# Earphone-5.net
KiCad netlist of a schematic drawn in Altium Designer
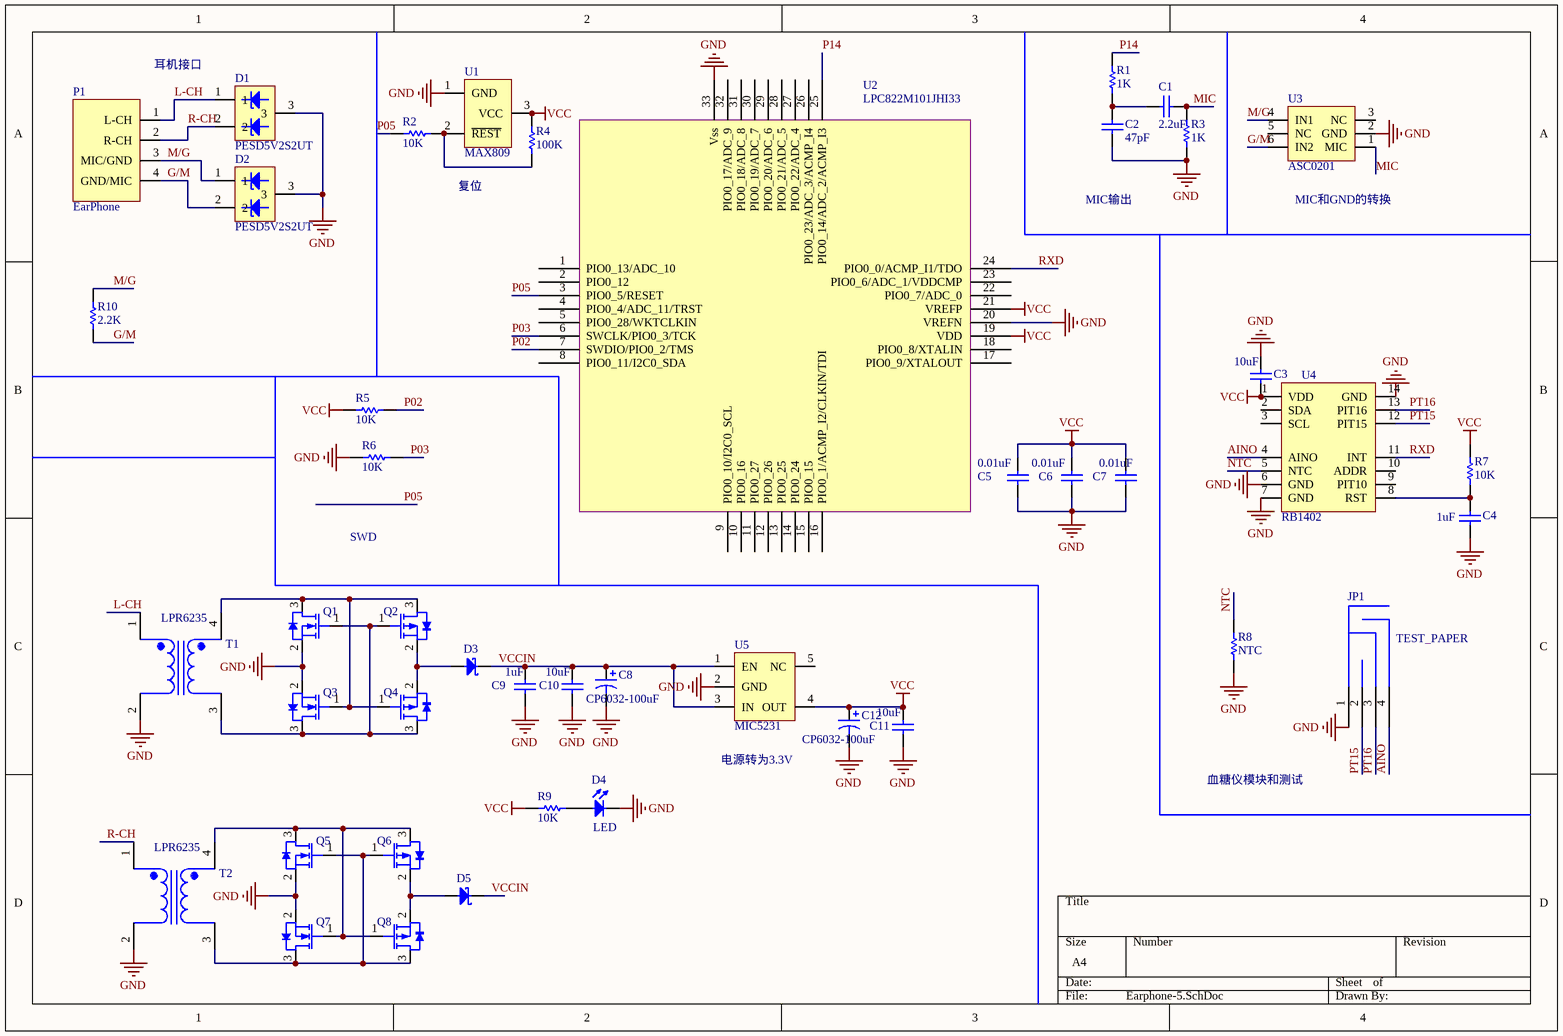
[diagram p0: Earphone-5.SchDoc]

(export (version "E")
  (design (tool "Eeschema 10.0.6"))
  (components
    (comp (ref "C1") (value "2.2uF") (footprint "0402C") (libsource (lib "Schlib1") (part "CAP")))
    (comp (ref "C2") (value "47pF") (footprint "0402C") (libsource (lib "Schlib1") (part "CAP")))
    (comp (ref "C3") (value "10uF") (footprint "0402C") (libsource (lib "Schlib1") (part "CAP")))
    (comp (ref "C4") (value "1uF") (footprint "0402C") (libsource (lib "Schlib1") (part "CAP")))
    (comp (ref "C5") (value "0.01uF") (footprint "0402C") (libsource (lib "Schlib1") (part "CAP")))
    (comp (ref "C6") (value "0.01uF") (footprint "0402C") (libsource (lib "Schlib1") (part "CAP")))
    (comp (ref "C7") (value "0.01uF") (footprint "0402C") (libsource (lib "Schlib1") (part "CAP")))
    (comp (ref "C8")
      (value "CP6032-100uF")
      (footprint "T3216-18[A]")
      (libsource (lib "Schlib1") (part "CAP POL2"))
    )
    (comp (ref "C9") (value "1uF") (footprint "0402C") (libsource (lib "Schlib1") (part "CAP")))
    (comp (ref "C10") (value "10uF") (footprint "0402C") (libsource (lib "Schlib1") (part "CAP")))
    (comp (ref "C11") (value "10uF") (footprint "0402C") (libsource (lib "Schlib1") (part "CAP")))
    (comp (ref "C12")
      (value "CP6032-100uF")
      (footprint "T3216-18[A]")
      (libsource (lib "Schlib1") (part "CAP POL2"))
    )
    (comp (ref "D1")
      (value "PESD5V2S2UT")
      (footprint "SOT23")
      (description "SOT23")
      (libsource (lib "Schlib1") (part "PESD5V2S2UT"))
    )
    (comp (ref "D2")
      (value "PESD5V2S2UT")
      (footprint "SOT23")
      (description "SOT23")
      (libsource (lib "Schlib1") (part "PESD5V2S2UT"))
    )
    (comp (ref "D3")
      (value "PMEG4002EJ")
      (footprint "SOD323")
      (description "SOD323F")
      (libsource (lib "Schlib1") (part "PMEG4002EJ"))
    )
    (comp (ref "D4") (value "LED") (footprint "0603L") (libsource (lib "Schlib1") (part "LED")))
    (comp (ref "D5")
      (value "PMEG4002EJ")
      (footprint "SOD323")
      (description "SOD323F")
      (libsource (lib "Schlib1") (part "PMEG4002EJ"))
    )
    (comp (ref "JP1")
      (value "TEST_PAPER")
      (footprint "TEST_PAPER")
      (libsource (lib "Schlib1") (part "TEST_PAPER"))
    )
    (comp (ref "P1") (value "EarPhone") (footprint "EarPhone") (libsource (lib "Schlib1") (part "EarPhone")))
    (comp (ref "Q1")
      (value "N-MOSFET")
      (footprint "SOT23")
      (description "4N80 N-Channel MOSFET")
      (libsource (lib "Schlib1") (part "N-MOSFET"))
    )
    (comp (ref "Q2")
      (value "P-MOSFET")
      (footprint "SOT23")
      (description "P-Channel MOSFET")
      (libsource (lib "Schlib1") (part "P-MOSFET"))
    )
    (comp (ref "Q3")
      (value "N-MOSFET")
      (footprint "SOT23")
      (description "4N80 N-Channel MOSFET")
      (libsource (lib "Schlib1") (part "N-MOSFET"))
    )
    (comp (ref "Q4")
      (value "P-MOSFET")
      (footprint "SOT23")
      (description "P-Channel MOSFET")
      (libsource (lib "") (part "P-MOSFET_1"))
    )
    (comp (ref "Q5")
      (value "N-MOSFET")
      (footprint "SOT23")
      (description "4N80 N-Channel MOSFET")
      (libsource (lib "Schlib1") (part "N-MOSFET"))
    )
    (comp (ref "Q6")
      (value "P-MOSFET")
      (footprint "SOT23")
      (description "P-Channel MOSFET")
      (libsource (lib "Schlib1") (part "P-MOSFET"))
    )
    (comp (ref "Q7")
      (value "N-MOSFET")
      (footprint "SOT23")
      (description "4N80 N-Channel MOSFET")
      (libsource (lib "Schlib1") (part "N-MOSFET"))
    )
    (comp (ref "Q8")
      (value "P-MOSFET")
      (footprint "SOT23")
      (description "P-Channel MOSFET")
      (libsource (lib "") (part "P-MOSFET_1"))
    )
    (comp (ref "R1") (value "1K") (footprint "0402R") (libsource (lib "Schlib1") (part "RES")))
    (comp (ref "R2") (value "10K") (footprint "0402R") (libsource (lib "Schlib1") (part "RES")))
    (comp (ref "R3") (value "1K") (footprint "0402R") (libsource (lib "Schlib1") (part "RES")))
    (comp (ref "R4") (value "100K") (footprint "0402R") (libsource (lib "Schlib1") (part "RES")))
    (comp (ref "R5") (value "10K") (footprint "0402R") (libsource (lib "Schlib1") (part "RES")))
    (comp (ref "R6") (value "10K") (footprint "0402R") (libsource (lib "Schlib1") (part "RES")))
    (comp (ref "R7") (value "10K") (footprint "0402R") (libsource (lib "Schlib1") (part "RES")))
    (comp (ref "R8") (value "NTC") (footprint "0603R") (libsource (lib "Schlib1") (part "RES")))
    (comp (ref "R9") (value "10K") (footprint "0402R") (libsource (lib "Schlib1") (part "RES")))
    (comp (ref "R10") (value "2.2K") (footprint "0402R") (libsource (lib "Schlib1") (part "RES")))
    (comp (ref "T1") (value "LPR6235") (footprint "Trans EMI") (libsource (lib "Schlib1") (part "Trans EMI")))
    (comp (ref "T2") (value "LPR6235") (footprint "Trans EMI") (libsource (lib "Schlib1") (part "Trans EMI")))
    (comp (ref "U1")
      (value "MAX809")
      (footprint "SOT23")
      (description "SOT23")
      (libsource (lib "Schlib1") (part "MAX809"))
    )
    (comp (ref "U2")
      (value "LPC822M101JHI33")
      (footprint "QFN50P500X500X100-33N")
      (libsource (lib "Schlib1") (part "LPC822M101JHI33"))
    )
    (comp (ref "U3")
      (value "ASC0201")
      (footprint "SOT23-6")
      (description "SOT23-6")
      (libsource (lib "Schlib1") (part "ASC0201"))
    )
    (comp (ref "U4") (value "RB1402") (footprint "RB1402") (libsource (lib "Schlib1") (part "RB1402")))
    (comp (ref "U5") (value "MIC5231") (footprint "SOT23-5") (libsource (lib "Schlib1") (part "MIC5231")))
  )
  (nets
    (net (code "1") (name "/AINO") (class "Default")
      (node (ref "JP1") (pin "4") (pinfunction "P_4") (pintype "passive"))
      (node (ref "U4") (pin "4") (pinfunction "AINO_4") (pintype "passive"))
    )
    (net (code "2") (name "/G{slash}M") (class "Default")
      (node (ref "D2") (pin "2") (pinfunction "2_2") (pintype "passive"))
      (node (ref "P1") (pin "4") (pinfunction "GND/MIC_4") (pintype "passive"))
      (node (ref "R10") (pin "1") (pinfunction "1_1") (pintype "passive"))
      (node (ref "U3") (pin "6") (pinfunction "IN2_6") (pintype "passive"))
    )
    (net (code "3") (name "/L-CH") (class "Default")
      (node (ref "D1") (pin "1") (pinfunction "1_1") (pintype "passive"))
      (node (ref "P1") (pin "1") (pinfunction "L-CH_1") (pintype "passive"))
      (node (ref "T1") (pin "1") (pinfunction "1_1") (pintype "passive"))
    )
    (net (code "4") (name "/MIC") (class "Default")
      (node (ref "C1") (pin "1") (pinfunction "1_1") (pintype "passive"))
      (node (ref "R3") (pin "1") (pinfunction "1_1") (pintype "passive"))
      (node (ref "U3") (pin "1") (pinfunction "MIC_1") (pintype "passive"))
    )
    (net (code "5") (name "/M{slash}G") (class "Default")
      (node (ref "D2") (pin "1") (pinfunction "1_1") (pintype "passive"))
      (node (ref "P1") (pin "3") (pinfunction "MIC/GND_3") (pintype "passive"))
      (node (ref "R10") (pin "2") (pinfunction "2_2") (pintype "passive"))
      (node (ref "U3") (pin "4") (pinfunction "IN1_4") (pintype "passive"))
    )
    (net (code "6") (name "/NTC") (class "Default")
      (node (ref "R8") (pin "2") (pinfunction "2_2") (pintype "passive"))
      (node (ref "U4") (pin "5") (pinfunction "NTC_5") (pintype "passive"))
    )
    (net (code "7") (name "/P02") (class "Default")
      (node (ref "R5") (pin "2") (pinfunction "2_2") (pintype "passive"))
      (node (ref "U2") (pin "7") (pinfunction "SWDIO/PIO0_2/TMS_7") (pintype "passive"))
    )
    (net (code "8") (name "/P03") (class "Default")
      (node (ref "R6") (pin "1") (pinfunction "1_1") (pintype "passive"))
      (node (ref "U2") (pin "6") (pinfunction "SWCLK/PIO0_3/TCK_6") (pintype "passive"))
    )
    (net (code "9") (name "/P05") (class "Default")
      (node (ref "R2") (pin "1") (pinfunction "1_1") (pintype "passive"))
      (node (ref "U2") (pin "3") (pinfunction "PIO0_5/RESET_3") (pintype "passive"))
    )
    (net (code "10") (name "/P14") (class "Default")
      (node (ref "R1") (pin "1") (pinfunction "1_1") (pintype "passive"))
      (node (ref "U2") (pin "25") (pinfunction "PIO0_14/ADC_2/ACMP_I3_25") (pintype "passive"))
    )
    (net (code "11") (name "/PT15") (class "Default")
      (node (ref "JP1") (pin "2") (pinfunction "PC10_2") (pintype "passive"))
      (node (ref "U4") (pin "12") (pinfunction "PIT15_12") (pintype "passive"))
    )
    (net (code "12") (name "/PT16") (class "Default")
      (node (ref "JP1") (pin "3") (pinfunction "NOP_3") (pintype "passive"))
      (node (ref "U4") (pin "13") (pinfunction "PIT16_13") (pintype "passive"))
    )
    (net (code "13") (name "/R-CH") (class "Default")
      (node (ref "D1") (pin "2") (pinfunction "2_2") (pintype "passive"))
      (node (ref "P1") (pin "2") (pinfunction "R-CH_2") (pintype "passive"))
      (node (ref "T2") (pin "1") (pinfunction "1_1") (pintype "passive"))
    )
    (net (code "14") (name "/RXD") (class "Default")
      (node (ref "U2") (pin "24") (pinfunction "PIO0_0/ACMP_I1/TDO_24") (pintype "passive"))
      (node (ref "U4") (pin "11") (pinfunction "INT_11") (pintype "passive"))
    )
    (net (code "15") (name "/VCCIN") (class "Default")
      (node (ref "C10") (pin "2") (pinfunction "2_2") (pintype "passive"))
      (node (ref "C8") (pin "1") (pinfunction "1_1") (pintype "passive"))
      (node (ref "C9") (pin "2") (pinfunction "2_2") (pintype "passive"))
      (node (ref "D3") (pin "1") (pinfunction "1_1") (pintype "passive"))
      (node (ref "D5") (pin "1") (pinfunction "1_1") (pintype "passive"))
      (node (ref "U5") (pin "1") (pinfunction "EN_1") (pintype "passive"))
      (node (ref "U5") (pin "3") (pinfunction "IN_3") (pintype "passive"))
    )
    (net (code "16") (name "GND") (class "Default")
      (node (ref "C10") (pin "1") (pinfunction "1_1") (pintype "passive"))
      (node (ref "C11") (pin "1") (pinfunction "1_1") (pintype "passive"))
      (node (ref "C12") (pin "2") (pinfunction "2_2") (pintype "passive"))
      (node (ref "C2") (pin "1") (pinfunction "1_1") (pintype "passive"))
      (node (ref "C3") (pin "2") (pinfunction "2_2") (pintype "passive"))
      (node (ref "C4") (pin "1") (pinfunction "1_1") (pintype "passive"))
      (node (ref "C5") (pin "1") (pinfunction "1_1") (pintype "passive"))
      (node (ref "C6") (pin "1") (pinfunction "1_1") (pintype "passive"))
      (node (ref "C7") (pin "1") (pinfunction "1_1") (pintype "passive"))
      (node (ref "C8") (pin "2") (pinfunction "2_2") (pintype "passive"))
      (node (ref "C9") (pin "1") (pinfunction "1_1") (pintype "passive"))
      (node (ref "D1") (pin "3") (pinfunction "3_3") (pintype "passive"))
      (node (ref "D2") (pin "3") (pinfunction "3_3") (pintype "passive"))
      (node (ref "D4") (pin "2") (pinfunction "K_2") (pintype "passive"))
      (node (ref "JP1") (pin "1") (pinfunction "N_1") (pintype "passive"))
      (node (ref "Q1") (pin "2") (pinfunction "S_2") (pintype "passive"))
      (node (ref "Q3") (pin "2") (pinfunction "S_2") (pintype "passive"))
      (node (ref "Q5") (pin "2") (pinfunction "S_2") (pintype "passive"))
      (node (ref "Q7") (pin "2") (pinfunction "S_2") (pintype "passive"))
      (node (ref "R3") (pin "2") (pinfunction "2_2") (pintype "passive"))
      (node (ref "R6") (pin "2") (pinfunction "2_2") (pintype "passive"))
      (node (ref "R8") (pin "1") (pinfunction "1_1") (pintype "passive"))
      (node (ref "T1") (pin "2") (pinfunction "2_2") (pintype "passive"))
      (node (ref "T2") (pin "2") (pinfunction "2_2") (pintype "passive"))
      (node (ref "U1") (pin "1") (pinfunction "GND_1") (pintype "passive"))
      (node (ref "U2") (pin "20") (pinfunction "VREFN_20") (pintype "passive"))
      (node (ref "U2") (pin "33") (pinfunction "Vss_33") (pintype "passive"))
      (node (ref "U3") (pin "2") (pinfunction "GND_2") (pintype "passive"))
      (node (ref "U4") (pin "14") (pinfunction "GND_14") (pintype "passive"))
      (node (ref "U4") (pin "6") (pinfunction "GND_6") (pintype "passive"))
      (node (ref "U4") (pin "7") (pinfunction "GND_7") (pintype "passive"))
      (node (ref "U5") (pin "2") (pinfunction "GND_2") (pintype "passive"))
    )
    (net (code "17") (name "Net-(C1-Pad2)") (class "Default")
      (node (ref "C1") (pin "2") (pinfunction "2_2") (pintype "passive"))
      (node (ref "C2") (pin "2") (pinfunction "2_2") (pintype "passive"))
      (node (ref "R1") (pin "2") (pinfunction "2_2") (pintype "passive"))
    )
    (net (code "18") (name "Net-(D4-A)") (class "Default")
      (node (ref "D4") (pin "1") (pinfunction "A_1") (pintype "passive"))
      (node (ref "R9") (pin "2") (pinfunction "2_2") (pintype "passive"))
    )
    (net (code "19") (name "Net-(Q1-D)") (class "Default")
      (node (ref "Q1") (pin "3") (pinfunction "D_3") (pintype "passive"))
      (node (ref "Q2") (pin "3") (pinfunction "D_3") (pintype "passive"))
      (node (ref "Q3") (pin "1") (pinfunction "G_1") (pintype "passive"))
      (node (ref "Q4") (pin "1") (pinfunction "G_1") (pintype "passive"))
      (node (ref "T1") (pin "4") (pinfunction "4_4") (pintype "passive"))
    )
    (net (code "20") (name "Net-(Q1-G)") (class "Default")
      (node (ref "Q1") (pin "1") (pinfunction "G_1") (pintype "passive"))
      (node (ref "Q2") (pin "1") (pinfunction "G_1") (pintype "passive"))
      (node (ref "Q3") (pin "3") (pinfunction "D_3") (pintype "passive"))
      (node (ref "Q4") (pin "3") (pinfunction "D_3") (pintype "passive"))
      (node (ref "T1") (pin "3") (pinfunction "3_3") (pintype "passive"))
    )
    (net (code "21") (name "Net-(Q2-S)") (class "Default")
      (node (ref "D3") (pin "2") (pinfunction "2_2") (pintype "passive"))
      (node (ref "Q2") (pin "2") (pinfunction "S_2") (pintype "passive"))
      (node (ref "Q4") (pin "2") (pinfunction "S_2") (pintype "passive"))
    )
    (net (code "22") (name "Net-(Q5-D)") (class "Default")
      (node (ref "Q5") (pin "3") (pinfunction "D_3") (pintype "passive"))
      (node (ref "Q6") (pin "3") (pinfunction "D_3") (pintype "passive"))
      (node (ref "Q7") (pin "1") (pinfunction "G_1") (pintype "passive"))
      (node (ref "Q8") (pin "1") (pinfunction "G_1") (pintype "passive"))
      (node (ref "T2") (pin "4") (pinfunction "4_4") (pintype "passive"))
    )
    (net (code "23") (name "Net-(Q5-G)") (class "Default")
      (node (ref "Q5") (pin "1") (pinfunction "G_1") (pintype "passive"))
      (node (ref "Q6") (pin "1") (pinfunction "G_1") (pintype "passive"))
      (node (ref "Q7") (pin "3") (pinfunction "D_3") (pintype "passive"))
      (node (ref "Q8") (pin "3") (pinfunction "D_3") (pintype "passive"))
      (node (ref "T2") (pin "3") (pinfunction "3_3") (pintype "passive"))
    )
    (net (code "24") (name "Net-(Q6-S)") (class "Default")
      (node (ref "D5") (pin "2") (pinfunction "2_2") (pintype "passive"))
      (node (ref "Q6") (pin "2") (pinfunction "S_2") (pintype "passive"))
      (node (ref "Q8") (pin "2") (pinfunction "S_2") (pintype "passive"))
    )
    (net (code "25") (name "Net-(U1-~{REST})") (class "Default")
      (node (ref "R2") (pin "2") (pinfunction "2_2") (pintype "passive"))
      (node (ref "R4") (pin "1") (pinfunction "1_1") (pintype "passive"))
      (node (ref "U1") (pin "2") (pinfunction "~{REST}_2") (pintype "passive"))
    )
    (net (code "26") (name "Net-(U4-RST)") (class "Default")
      (node (ref "C4") (pin "2") (pinfunction "2_2") (pintype "passive"))
      (node (ref "R7") (pin "1") (pinfunction "1_1") (pintype "passive"))
      (node (ref "U4") (pin "8") (pinfunction "RST_8") (pintype "passive"))
    )
    (net (code "27") (name "VCC") (class "Default")
      (node (ref "C11") (pin "2") (pinfunction "2_2") (pintype "passive"))
      (node (ref "C12") (pin "1") (pinfunction "1_1") (pintype "passive"))
      (node (ref "C3") (pin "1") (pinfunction "1_1") (pintype "passive"))
      (node (ref "C5") (pin "2") (pinfunction "2_2") (pintype "passive"))
      (node (ref "C6") (pin "2") (pinfunction "2_2") (pintype "passive"))
      (node (ref "C7") (pin "2") (pinfunction "2_2") (pintype "passive"))
      (node (ref "R4") (pin "2") (pinfunction "2_2") (pintype "passive"))
      (node (ref "R5") (pin "1") (pinfunction "1_1") (pintype "passive"))
      (node (ref "R7") (pin "2") (pinfunction "2_2") (pintype "passive"))
      (node (ref "R9") (pin "1") (pinfunction "1_1") (pintype "passive"))
      (node (ref "U1") (pin "3") (pinfunction "VCC_3") (pintype "passive"))
      (node (ref "U2") (pin "19") (pinfunction "VDD_19") (pintype "passive"))
      (node (ref "U2") (pin "21") (pinfunction "VREFP_21") (pintype "passive"))
      (node (ref "U4") (pin "1") (pinfunction "VDD_1") (pintype "passive"))
      (node (ref "U5") (pin "4") (pinfunction "OUT_4") (pintype "passive"))
    )
    (net (code "28") (name "unconnected-(U2-PIO0_1{slash}ACMP_I2{slash}CLKIN{slash}TDI-Pad16)") (class "Default")
      (node (ref "U2") (pin "16") (pinfunction "PIO0_1/ACMP_I2/CLKIN/TDI_16") (pintype "passive"))
    )
    (net (code "29") (name "unconnected-(U2-PIO0_4{slash}ADC_11{slash}TRST-Pad4)") (class "Default")
      (node (ref "U2") (pin "4") (pinfunction "PIO0_4/ADC_11/TRST_4") (pintype "passive"))
    )
    (net (code "30") (name "unconnected-(U2-PIO0_6{slash}ADC_1{slash}VDDCMP-Pad23)") (class "Default")
      (node (ref "U2") (pin "23") (pinfunction "PIO0_6/ADC_1/VDDCMP_23") (pintype "passive"))
    )
    (net (code "31") (name "unconnected-(U2-PIO0_7{slash}ADC_0-Pad22)") (class "Default")
      (node (ref "U2") (pin "22") (pinfunction "PIO0_7/ADC_0_22") (pintype "passive"))
    )
    (net (code "32") (name "unconnected-(U2-PIO0_8{slash}XTALIN-Pad18)") (class "Default")
      (node (ref "U2") (pin "18") (pinfunction "PIO0_8/XTALIN_18") (pintype "passive"))
    )
    (net (code "33") (name "unconnected-(U2-PIO0_9{slash}XTALOUT-Pad17)") (class "Default")
      (node (ref "U2") (pin "17") (pinfunction "PIO0_9/XTALOUT_17") (pintype "passive"))
    )
    (net (code "34") (name "unconnected-(U2-PIO0_10{slash}I2C0_SCL-Pad9)") (class "Default")
      (node (ref "U2") (pin "9") (pinfunction "PIO0_10/I2C0_SCL_9") (pintype "passive"))
    )
    (net (code "35") (name "unconnected-(U2-PIO0_11{slash}I2C0_SDA-Pad8)") (class "Default")
      (node (ref "U2") (pin "8") (pinfunction "PIO0_11/I2C0_SDA_8") (pintype "passive"))
    )
    (net (code "36") (name "unconnected-(U2-PIO0_12-Pad2)") (class "Default")
      (node (ref "U2") (pin "2") (pinfunction "PIO0_12_2") (pintype "passive"))
    )
    (net (code "37") (name "unconnected-(U2-PIO0_13{slash}ADC_10-Pad1)") (class "Default")
      (node (ref "U2") (pin "1") (pinfunction "PIO0_13/ADC_10_1") (pintype "passive"))
    )
    (net (code "38") (name "unconnected-(U2-PIO0_15-Pad15)") (class "Default")
      (node (ref "U2") (pin "15") (pinfunction "PIO0_15_15") (pintype "passive"))
    )
    (net (code "39") (name "unconnected-(U2-PIO0_16-Pad10)") (class "Default")
      (node (ref "U2") (pin "10") (pinfunction "PIO0_16_10") (pintype "passive"))
    )
    (net (code "40") (name "unconnected-(U2-PIO0_17{slash}ADC_9-Pad32)") (class "Default")
      (node (ref "U2") (pin "32") (pinfunction "PIO0_17/ADC_9_32") (pintype "passive"))
    )
    (net (code "41") (name "unconnected-(U2-PIO0_18{slash}ADC_8-Pad31)") (class "Default")
      (node (ref "U2") (pin "31") (pinfunction "PIO0_18/ADC_8_31") (pintype "passive"))
    )
    (net (code "42") (name "unconnected-(U2-PIO0_19{slash}ADC_7-Pad30)") (class "Default")
      (node (ref "U2") (pin "30") (pinfunction "PIO0_19/ADC_7_30") (pintype "passive"))
    )
    (net (code "43") (name "unconnected-(U2-PIO0_20{slash}ADC_6-Pad29)") (class "Default")
      (node (ref "U2") (pin "29") (pinfunction "PIO0_20/ADC_6_29") (pintype "passive"))
    )
    (net (code "44") (name "unconnected-(U2-PIO0_21{slash}ADC_5-Pad28)") (class "Default")
      (node (ref "U2") (pin "28") (pinfunction "PIO0_21/ADC_5_28") (pintype "passive"))
    )
    (net (code "45") (name "unconnected-(U2-PIO0_22{slash}ADC_4-Pad27)") (class "Default")
      (node (ref "U2") (pin "27") (pinfunction "PIO0_22/ADC_4_27") (pintype "passive"))
    )
    (net (code "46") (name "unconnected-(U2-PIO0_23{slash}ADC_3{slash}ACMP_I4-Pad26)") (class "Default")
      (node (ref "U2") (pin "26") (pinfunction "PIO0_23/ADC_3/ACMP_I4_26") (pintype "passive"))
    )
    (net (code "47") (name "unconnected-(U2-PIO0_24-Pad14)") (class "Default")
      (node (ref "U2") (pin "14") (pinfunction "PIO0_24_14") (pintype "passive"))
    )
    (net (code "48") (name "unconnected-(U2-PIO0_25-Pad13)") (class "Default")
      (node (ref "U2") (pin "13") (pinfunction "PIO0_25_13") (pintype "passive"))
    )
    (net (code "49") (name "unconnected-(U2-PIO0_26-Pad12)") (class "Default")
      (node (ref "U2") (pin "12") (pinfunction "PIO0_26_12") (pintype "passive"))
    )
    (net (code "50") (name "unconnected-(U2-PIO0_27-Pad11)") (class "Default")
      (node (ref "U2") (pin "11") (pinfunction "PIO0_27_11") (pintype "passive"))
    )
    (net (code "51") (name "unconnected-(U2-PIO0_28{slash}WKTCLKIN-Pad5)") (class "Default")
      (node (ref "U2") (pin "5") (pinfunction "PIO0_28/WKTCLKIN_5") (pintype "passive"))
    )
    (net (code "52") (name "unconnected-(U3-NC-Pad3)") (class "Default")
      (node (ref "U3") (pin "3") (pinfunction "NC_3") (pintype "passive"))
    )
    (net (code "53") (name "unconnected-(U3-NC-Pad5)") (class "Default")
      (node (ref "U3") (pin "5") (pinfunction "NC_5") (pintype "passive"))
    )
    (net (code "54") (name "unconnected-(U4-ADDR-Pad10)") (class "Default")
      (node (ref "U4") (pin "10") (pinfunction "ADDR_10") (pintype "passive"))
    )
    (net (code "55") (name "unconnected-(U4-PIT10-Pad9)") (class "Default")
      (node (ref "U4") (pin "9") (pinfunction "PIT10_9") (pintype "passive"))
    )
    (net (code "56") (name "unconnected-(U4-SCL-Pad3)") (class "Default")
      (node (ref "U4") (pin "3") (pinfunction "SCL_3") (pintype "passive"))
    )
    (net (code "57") (name "unconnected-(U4-SDA-Pad2)") (class "Default")
      (node (ref "U4") (pin "2") (pinfunction "SDA_2") (pintype "passive"))
    )
    (net (code "58") (name "unconnected-(U5-NC-Pad5)") (class "Default")
      (node (ref "U5") (pin "5") (pinfunction "NC_5") (pintype "passive"))
    )
  )
)
